# SE880_module_EFM32LG-STK3600.net
KiCad netlist of a schematic drawn in EAGLE
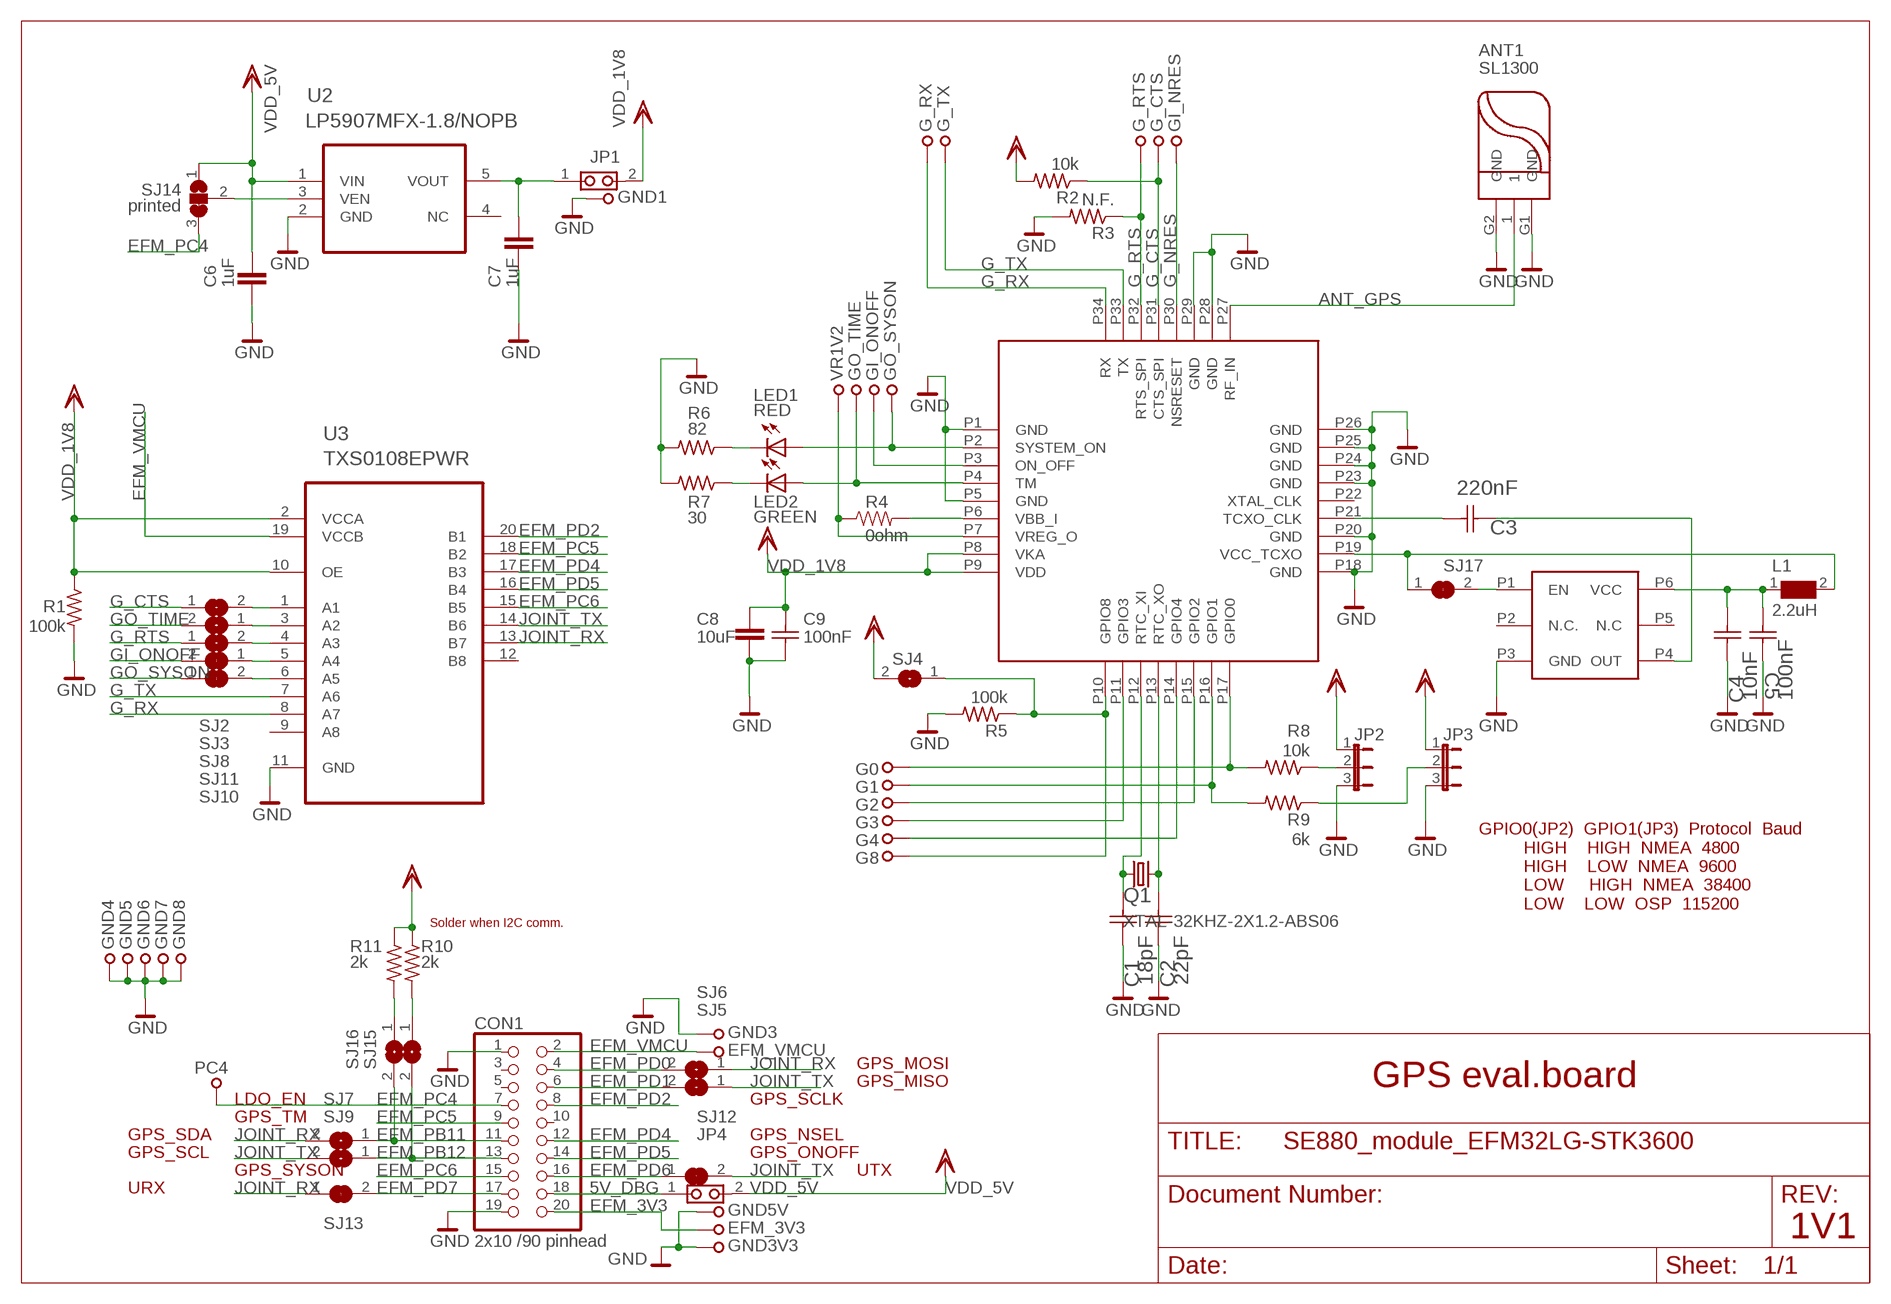
[diagram p0: schematic, sheet 1]

(export (version "E")
  (design (tool "Eeschema 10.0.6"))
  (components
    (comp (ref "ANT1")
      (value "SL1300")
      (footprint "eagle-import:SL1300")
      (libsource (lib "eagle-import") (part "SL1300"))
    )
    (comp (ref "C1")
      (value "18pF")
      (footprint "eagle-import:CAPC1005X60N")
      (libsource (lib "eagle-import") (part "CAP_GRM15"))
    )
    (comp (ref "C2")
      (value "22pF")
      (footprint "eagle-import:CAPC1005X60N")
      (libsource (lib "eagle-import") (part "CAP_GRM15"))
    )
    (comp (ref "C3")
      (value "220nF")
      (footprint "eagle-import:CAPC1005X60N")
      (libsource (lib "eagle-import") (part "CAP_GRM15"))
    )
    (comp (ref "C4")
      (value "10nF")
      (footprint "eagle-import:CAPC1005X60N")
      (libsource (lib "eagle-import") (part "CAP_GRM15"))
    )
    (comp (ref "C5")
      (value "100nF")
      (footprint "eagle-import:CAPC1005X60N")
      (libsource (lib "eagle-import") (part "CAP_GRM15"))
    )
    (comp (ref "C6")
      (value "1uF")
      (footprint "eagle-import:0603")
      (libsource (lib "eagle-import") (part "CAP-SMD0603"))
    )
    (comp (ref "C7")
      (value "1uF")
      (footprint "eagle-import:0603")
      (libsource (lib "eagle-import") (part "CAP-SMD0603"))
    )
    (comp (ref "C8")
      (value "10uF")
      (footprint "eagle-import:0603")
      (libsource (lib "eagle-import") (part "CAP-SMD0603"))
    )
    (comp (ref "C9")
      (value "100nF")
      (footprint "eagle-import:CAPC1005X60N")
      (libsource (lib "eagle-import") (part "CAP_GRM15"))
    )
    (comp (ref "CON1")
      (value "2x10 /90 pinhead")
      (footprint "eagle-import:2X10_90_FEMALE_EFM_MUTANT")
      (libsource (lib "eagle-import") (part "PINHD-2X10/90_FEMALE_EFM"))
    )
    (comp (ref "EFM_3V3")
      (value "TESTPOINT39MIL")
      (footprint "eagle-import:TESTPOINT1,0")
      (libsource (lib "eagle-import") (part "TESTPOINT39MIL"))
    )
    (comp (ref "EFM_VMCU")
      (value "TESTPOINT39MIL")
      (footprint "eagle-import:TESTPOINT1,0")
      (libsource (lib "eagle-import") (part "TESTPOINT39MIL"))
    )
    (comp (ref "G0")
      (value "TESTPOINT39MIL")
      (footprint "eagle-import:TESTPOINT1,0")
      (libsource (lib "eagle-import") (part "TESTPOINT39MIL"))
    )
    (comp (ref "G1")
      (value "TESTPOINT39MIL")
      (footprint "eagle-import:TESTPOINT1,0")
      (libsource (lib "eagle-import") (part "TESTPOINT39MIL"))
    )
    (comp (ref "G2")
      (value "TESTPOINT39MIL")
      (footprint "eagle-import:TESTPOINT1,0")
      (libsource (lib "eagle-import") (part "TESTPOINT39MIL"))
    )
    (comp (ref "G3")
      (value "TESTPOINT39MIL")
      (footprint "eagle-import:TESTPOINT1,0")
      (libsource (lib "eagle-import") (part "TESTPOINT39MIL"))
    )
    (comp (ref "G4")
      (value "TESTPOINT39MIL")
      (footprint "eagle-import:TESTPOINT1,0")
      (libsource (lib "eagle-import") (part "TESTPOINT39MIL"))
    )
    (comp (ref "G8")
      (value "TESTPOINT39MIL")
      (footprint "eagle-import:TESTPOINT1,0")
      (libsource (lib "eagle-import") (part "TESTPOINT39MIL"))
    )
    (comp (ref "GI_NRES")
      (value "TESTPOINT39MIL")
      (footprint "eagle-import:TESTPOINT1,0")
      (libsource (lib "eagle-import") (part "TESTPOINT39MIL"))
    )
    (comp (ref "GI_ONOFF")
      (value "TESTPOINT39MIL")
      (footprint "eagle-import:TESTPOINT1,0")
      (libsource (lib "eagle-import") (part "TESTPOINT39MIL"))
    )
    (comp (ref "GND1")
      (value "TESTPOINT39MIL")
      (footprint "eagle-import:TESTPOINT1,0")
      (libsource (lib "eagle-import") (part "TESTPOINT39MIL"))
    )
    (comp (ref "GND3")
      (value "TESTPOINT39MIL")
      (footprint "eagle-import:TESTPOINT1,0")
      (libsource (lib "eagle-import") (part "TESTPOINT39MIL"))
    )
    (comp (ref "GND3V3")
      (value "TESTPOINT39MIL")
      (footprint "eagle-import:TESTPOINT1,0")
      (libsource (lib "eagle-import") (part "TESTPOINT39MIL"))
    )
    (comp (ref "GND4")
      (value "TESTPOINT39MIL")
      (footprint "eagle-import:TESTPOINT1,0")
      (libsource (lib "eagle-import") (part "TESTPOINT39MIL"))
    )
    (comp (ref "GND5")
      (value "TESTPOINT39MIL")
      (footprint "eagle-import:TESTPOINT1,0")
      (libsource (lib "eagle-import") (part "TESTPOINT39MIL"))
    )
    (comp (ref "GND5V")
      (value "TESTPOINT39MIL")
      (footprint "eagle-import:TESTPOINT1,0")
      (libsource (lib "eagle-import") (part "TESTPOINT39MIL"))
    )
    (comp (ref "GND6")
      (value "TESTPOINT39MIL")
      (footprint "eagle-import:TESTPOINT1,0")
      (libsource (lib "eagle-import") (part "TESTPOINT39MIL"))
    )
    (comp (ref "GND7")
      (value "TESTPOINT39MIL")
      (footprint "eagle-import:TESTPOINT1,0")
      (libsource (lib "eagle-import") (part "TESTPOINT39MIL"))
    )
    (comp (ref "GND8")
      (value "TESTPOINT39MIL")
      (footprint "eagle-import:TESTPOINT1,0")
      (libsource (lib "eagle-import") (part "TESTPOINT39MIL"))
    )
    (comp (ref "GO_SYSON")
      (value "TESTPOINT39MIL")
      (footprint "eagle-import:TESTPOINT1,0")
      (libsource (lib "eagle-import") (part "TESTPOINT39MIL"))
    )
    (comp (ref "GO_TIME")
      (value "TESTPOINT39MIL")
      (footprint "eagle-import:TESTPOINT1,0")
      (libsource (lib "eagle-import") (part "TESTPOINT39MIL"))
    )
    (comp (ref "G_CTS")
      (value "TESTPOINT39MIL")
      (footprint "eagle-import:TESTPOINT1,0")
      (libsource (lib "eagle-import") (part "TESTPOINT39MIL"))
    )
    (comp (ref "G_RTS")
      (value "TESTPOINT39MIL")
      (footprint "eagle-import:TESTPOINT1,0")
      (libsource (lib "eagle-import") (part "TESTPOINT39MIL"))
    )
    (comp (ref "G_RX")
      (value "TESTPOINT39MIL")
      (footprint "eagle-import:TESTPOINT1,0")
      (libsource (lib "eagle-import") (part "TESTPOINT39MIL"))
    )
    (comp (ref "G_TX")
      (value "TESTPOINT39MIL")
      (footprint "eagle-import:TESTPOINT1,0")
      (libsource (lib "eagle-import") (part "TESTPOINT39MIL"))
    )
    (comp (ref "JP1")
      (value "JUMPER2-A")
      (footprint "eagle-import:PIN2-1R")
      (libsource (lib "eagle-import") (part "JUMPER2-A"))
    )
    (comp (ref "JP2")
      (value "jumper 2mm")
      (footprint "eagle-import:JP2")
      (libsource (lib "eagle-import") (part "JP2E"))
    )
    (comp (ref "JP3")
      (value "jumper 2mm")
      (footprint "eagle-import:JP2")
      (libsource (lib "eagle-import") (part "JP2E"))
    )
    (comp (ref "JP4")
      (value "JUMPER2-A")
      (footprint "eagle-import:PIN2-1R")
      (libsource (lib "eagle-import") (part "JUMPER2-A"))
    )
    (comp (ref "L1")
      (value "2.2uH")
      (footprint "eagle-import:WE-KI_1008_B")
      (libsource (lib "eagle-import") (part "WE-KI_1008_B"))
    )
    (comp (ref "LED1")
      (value "RED")
      (footprint "eagle-import:LED-0603")
      (libsource (lib "eagle-import") (part "LED0603"))
    )
    (comp (ref "LED2")
      (value "GREEN")
      (footprint "eagle-import:LED-0603")
      (libsource (lib "eagle-import") (part "LED0603"))
    )
    (comp (ref "PC4")
      (value "TESTPOINT39MIL")
      (footprint "eagle-import:TESTPOINT1,0")
      (libsource (lib "eagle-import") (part "TESTPOINT39MIL"))
    )
    (comp (ref "Q1")
      (value "XTAL-32KHZ-2X1.2-ABS06")
      (footprint "eagle-import:CRYSTAL-SMD-2X1.2-ABS06")
      (libsource (lib "eagle-import") (part "XTAL-32KHZ-2X1.2-ABS06"))
    )
    (comp (ref "Q3")
      (value "KT2520F16369ACW18TAN")
      (footprint "eagle-import:TCXO_2.5X2MM")
      (libsource (lib "eagle-import") (part "TCXO-KT2520-16M369"))
    )
    (comp (ref "R1")
      (value "100k")
      (footprint "eagle-import:R0402")
      (libsource (lib "eagle-import") (part "R-US_R0402"))
    )
    (comp (ref "R2")
      (value "10k")
      (footprint "eagle-import:R0402")
      (libsource (lib "eagle-import") (part "R-US_R0402"))
    )
    (comp (ref "R3")
      (value "N.F.")
      (footprint "eagle-import:R0402")
      (libsource (lib "eagle-import") (part "R-US_R0402"))
    )
    (comp (ref "R4")
      (value "0ohm")
      (footprint "eagle-import:0603-RES")
      (libsource (lib "eagle-import") (part "RESISTOR0603-RES"))
    )
    (comp (ref "R5")
      (value "100k")
      (footprint "eagle-import:R0402")
      (libsource (lib "eagle-import") (part "R-US_R0402"))
    )
    (comp (ref "R6")
      (value "82")
      (footprint "eagle-import:R0402")
      (libsource (lib "eagle-import") (part "R-US_R0402"))
    )
    (comp (ref "R7")
      (value "30")
      (footprint "eagle-import:R0402")
      (libsource (lib "eagle-import") (part "R-US_R0402"))
    )
    (comp (ref "R8")
      (value "10k")
      (footprint "eagle-import:R0402")
      (libsource (lib "eagle-import") (part "R-US_R0402"))
    )
    (comp (ref "R9")
      (value "6k")
      (footprint "eagle-import:R0402")
      (libsource (lib "eagle-import") (part "R-US_R0402"))
    )
    (comp (ref "R10")
      (value "2k")
      (footprint "eagle-import:R0402")
      (libsource (lib "eagle-import") (part "R-US_R0402"))
    )
    (comp (ref "R11")
      (value "2k")
      (footprint "eagle-import:R0402")
      (libsource (lib "eagle-import") (part "R-US_R0402"))
    )
    (comp (ref "SJ2")
      (value "printed")
      (footprint "eagle-import:JUMPER_SMD_SJ")
      (libsource (lib "eagle-import") (part "JUMPER_SMD"))
    )
    (comp (ref "SJ3")
      (value "printed")
      (footprint "eagle-import:JUMPER_SMD_SJ")
      (libsource (lib "eagle-import") (part "JUMPER_SMD"))
    )
    (comp (ref "SJ4")
      (value "printed")
      (footprint "eagle-import:JUMPER_SMD_SJ")
      (libsource (lib "eagle-import") (part "JUMPER_SMD"))
    )
    (comp (ref "SJ5")
      (value "printed")
      (footprint "eagle-import:JUMPER_SMD_SJ")
      (libsource (lib "eagle-import") (part "JUMPER_SMD"))
    )
    (comp (ref "SJ6")
      (value "printed")
      (footprint "eagle-import:JUMPER_SMD_SJ")
      (libsource (lib "eagle-import") (part "JUMPER_SMD"))
    )
    (comp (ref "SJ7")
      (value "printed")
      (footprint "eagle-import:JUMPER_SMD_SJ")
      (libsource (lib "eagle-import") (part "JUMPER_SMD"))
    )
    (comp (ref "SJ8")
      (value "printed")
      (footprint "eagle-import:JUMPER_SMD_SJ")
      (libsource (lib "eagle-import") (part "JUMPER_SMD"))
    )
    (comp (ref "SJ9")
      (value "printed")
      (footprint "eagle-import:JUMPER_SMD_SJ")
      (libsource (lib "eagle-import") (part "JUMPER_SMD"))
    )
    (comp (ref "SJ10")
      (value "printed")
      (footprint "eagle-import:JUMPER_SMD_SJ_1")
      (libsource (lib "eagle-import") (part "JUMPER_SMD_1"))
    )
    (comp (ref "SJ11")
      (value "printed")
      (footprint "eagle-import:JUMPER_SMD_SJ_1")
      (libsource (lib "eagle-import") (part "JUMPER_SMD_1"))
    )
    (comp (ref "SJ12")
      (value "printed")
      (footprint "eagle-import:JUMPER_SMD_SJ_1")
      (libsource (lib "eagle-import") (part "JUMPER_SMD_1"))
    )
    (comp (ref "SJ13")
      (value "printed")
      (footprint "eagle-import:JUMPER_SMD_SJ_1")
      (libsource (lib "eagle-import") (part "JUMPER_SMD_1"))
    )
    (comp (ref "SJ14")
      (value "printed")
      (footprint "eagle-import:JUMPER_SMD_SJ2A")
      (libsource (lib "eagle-import") (part "JUMPER_SMD_3A"))
    )
    (comp (ref "SJ15")
      (value "printed")
      (footprint "eagle-import:JUMPER_SMD_SJ")
      (libsource (lib "eagle-import") (part "JUMPER_SMD"))
    )
    (comp (ref "SJ16")
      (value "printed")
      (footprint "eagle-import:JUMPER_SMD_SJ")
      (libsource (lib "eagle-import") (part "JUMPER_SMD"))
    )
    (comp (ref "SJ17")
      (value "printed")
      (footprint "eagle-import:JUMPER_SMD_SJ_1")
      (libsource (lib "eagle-import") (part "JUMPER_SMD_1"))
    )
    (comp (ref "U1")
      (value "Telit SE880 GPS receiver")
      (footprint "eagle-import:LGA-34")
      (libsource (lib "eagle-import") (part "SE880"))
    )
    (comp (ref "U2")
      (value "LP5907MFX-1.8/NOPB")
      (footprint "eagle-import:SOT-23_5-NEW")
      (libsource (lib "eagle-import") (part "LP5907MFX-1.8/NOPB"))
    )
    (comp (ref "U3")
      (value "TXS0108EPWR")
      (footprint "eagle-import:SOP65P640X120-20N")
      (libsource (lib "eagle-import") (part "TXB0108PWR"))
    )
    (comp (ref "VR1V2")
      (value "TESTPOINT39MIL")
      (footprint "eagle-import:TESTPOINT1,0")
      (libsource (lib "eagle-import") (part "TESTPOINT39MIL"))
    )
  )
  (nets
    (net (code "1") (name "/5V_DBG") (class "Default")
      (node (ref "CON1") (pin "18") (pinfunction "18_18") (pintype "passive"))
      (node (ref "JP4") (pin "1") (pinfunction "A_1") (pintype "passive"))
    )
    (net (code "2") (name "/ANT_GPS") (class "Default")
      (node (ref "ANT1") (pin "1") (pinfunction "1_1") (pintype "bidirectional"))
      (node (ref "U1") (pin "P27") (pinfunction "RF_IN_P27") (pintype "bidirectional"))
    )
    (net (code "3") (name "/EFM_3V3") (class "Default")
      (node (ref "CON1") (pin "20") (pinfunction "20_20") (pintype "passive"))
      (node (ref "EFM_3V3") (pin "1") (pinfunction "P$1_1") (pintype "passive"))
    )
    (net (code "4") (name "/EFM_PB11") (class "Default")
      (node (ref "CON1") (pin "11") (pinfunction "11_11") (pintype "passive"))
      (node (ref "SJ16") (pin "2") (pinfunction "2_2") (pintype "passive"))
      (node (ref "SJ7") (pin "1") (pinfunction "1_1") (pintype "passive"))
    )
    (net (code "5") (name "/EFM_PB12") (class "Default")
      (node (ref "CON1") (pin "13") (pinfunction "13_13") (pintype "passive"))
      (node (ref "SJ15") (pin "2") (pinfunction "2_2") (pintype "passive"))
      (node (ref "SJ9") (pin "1") (pinfunction "1_1") (pintype "passive"))
    )
    (net (code "6") (name "/EFM_PC4") (class "Default")
      (node (ref "CON1") (pin "7") (pinfunction "7_7") (pintype "passive"))
      (node (ref "PC4") (pin "1") (pinfunction "P$1_1") (pintype "passive"))
      (node (ref "SJ14") (pin "3") (pinfunction "3_3") (pintype "passive"))
    )
    (net (code "7") (name "/EFM_PC5") (class "Default")
      (node (ref "CON1") (pin "9") (pinfunction "9_9") (pintype "passive"))
      (node (ref "U3") (pin "18") (pinfunction "B2_18") (pintype "bidirectional"))
    )
    (net (code "8") (name "/EFM_PC6") (class "Default")
      (node (ref "CON1") (pin "15") (pinfunction "15_15") (pintype "passive"))
      (node (ref "U3") (pin "15") (pinfunction "B5_15") (pintype "bidirectional"))
    )
    (net (code "9") (name "/EFM_PD0") (class "Default")
      (node (ref "CON1") (pin "4") (pinfunction "4_4") (pintype "passive"))
      (node (ref "SJ6") (pin "2") (pinfunction "2_2") (pintype "passive"))
    )
    (net (code "10") (name "/EFM_PD1") (class "Default")
      (node (ref "CON1") (pin "6") (pinfunction "6_6") (pintype "passive"))
      (node (ref "SJ5") (pin "2") (pinfunction "2_2") (pintype "passive"))
    )
    (net (code "11") (name "/EFM_PD2") (class "Default")
      (node (ref "CON1") (pin "8") (pinfunction "8_8") (pintype "passive"))
      (node (ref "U3") (pin "20") (pinfunction "B1_20") (pintype "bidirectional"))
    )
    (net (code "12") (name "/EFM_PD4") (class "Default")
      (node (ref "CON1") (pin "12") (pinfunction "12_12") (pintype "passive"))
      (node (ref "U3") (pin "17") (pinfunction "B3_17") (pintype "bidirectional"))
    )
    (net (code "13") (name "/EFM_PD5") (class "Default")
      (node (ref "CON1") (pin "14") (pinfunction "14_14") (pintype "passive"))
      (node (ref "U3") (pin "16") (pinfunction "B4_16") (pintype "bidirectional"))
    )
    (net (code "14") (name "/EFM_PD6") (class "Default")
      (node (ref "CON1") (pin "16") (pinfunction "16_16") (pintype "passive"))
      (node (ref "SJ12") (pin "1") (pinfunction "1_1") (pintype "passive"))
    )
    (net (code "15") (name "/EFM_PD7") (class "Default")
      (node (ref "CON1") (pin "17") (pinfunction "17_17") (pintype "passive"))
      (node (ref "SJ13") (pin "2") (pinfunction "2_2") (pintype "passive"))
    )
    (net (code "16") (name "/EFM_VMCU") (class "Default")
      (node (ref "CON1") (pin "2") (pinfunction "2_2") (pintype "passive"))
      (node (ref "EFM_VMCU") (pin "1") (pinfunction "P$1_1") (pintype "passive"))
      (node (ref "U3") (pin "19") (pinfunction "VCCB_19") (pintype "power_in"))
    )
    (net (code "17") (name "/GI_ONOFF") (class "Default")
      (node (ref "GI_ONOFF") (pin "1") (pinfunction "P$1_1") (pintype "passive"))
      (node (ref "SJ11") (pin "2") (pinfunction "2_2") (pintype "passive"))
      (node (ref "U1") (pin "P3") (pinfunction "ON_OFF_P3") (pintype "bidirectional"))
    )
    (net (code "18") (name "/GO_SYSON") (class "Default")
      (node (ref "GO_SYSON") (pin "1") (pinfunction "P$1_1") (pintype "passive"))
      (node (ref "LED1") (pin "A") (pinfunction "A_A") (pintype "passive"))
      (node (ref "SJ10") (pin "1") (pinfunction "1_1") (pintype "passive"))
      (node (ref "U1") (pin "P2") (pinfunction "SYSTEM_ON_P2") (pintype "bidirectional"))
    )
    (net (code "19") (name "/GO_TIME") (class "Default")
      (node (ref "GO_TIME") (pin "1") (pinfunction "P$1_1") (pintype "passive"))
      (node (ref "LED2") (pin "A") (pinfunction "A_A") (pintype "passive"))
      (node (ref "SJ3") (pin "2") (pinfunction "2_2") (pintype "passive"))
      (node (ref "U1") (pin "P4") (pinfunction "TM_P4") (pintype "bidirectional"))
    )
    (net (code "20") (name "/G_CTS") (class "Default")
      (node (ref "G_CTS") (pin "1") (pinfunction "P$1_1") (pintype "passive"))
      (node (ref "R2") (pin "1") (pinfunction "1_1") (pintype "passive"))
      (node (ref "SJ2") (pin "1") (pinfunction "1_1") (pintype "passive"))
      (node (ref "U1") (pin "P31") (pinfunction "CTS_SPI_P31") (pintype "bidirectional"))
    )
    (net (code "21") (name "/G_NRES") (class "Default")
      (node (ref "GI_NRES") (pin "1") (pinfunction "P$1_1") (pintype "passive"))
      (node (ref "U1") (pin "P30") (pinfunction "NSRESET_P30") (pintype "bidirectional"))
    )
    (net (code "22") (name "/G_RTS") (class "Default")
      (node (ref "G_RTS") (pin "1") (pinfunction "P$1_1") (pintype "passive"))
      (node (ref "R3") (pin "1") (pinfunction "1_1") (pintype "passive"))
      (node (ref "SJ8") (pin "1") (pinfunction "1_1") (pintype "passive"))
      (node (ref "U1") (pin "P32") (pinfunction "RTS_SPI_P32") (pintype "bidirectional"))
    )
    (net (code "23") (name "/G_RX") (class "Default")
      (node (ref "G_RX") (pin "1") (pinfunction "P$1_1") (pintype "passive"))
      (node (ref "U1") (pin "P34") (pinfunction "RX_P34") (pintype "bidirectional"))
      (node (ref "U3") (pin "8") (pinfunction "A7_8") (pintype "bidirectional"))
    )
    (net (code "24") (name "/G_TX") (class "Default")
      (node (ref "G_TX") (pin "1") (pinfunction "P$1_1") (pintype "passive"))
      (node (ref "U1") (pin "P33") (pinfunction "TX_P33") (pintype "bidirectional"))
      (node (ref "U3") (pin "7") (pinfunction "A6_7") (pintype "bidirectional"))
    )
    (net (code "25") (name "/JOINT_RX") (class "Default")
      (node (ref "SJ13") (pin "1") (pinfunction "1_1") (pintype "passive"))
      (node (ref "SJ6") (pin "1") (pinfunction "1_1") (pintype "passive"))
      (node (ref "SJ7") (pin "2") (pinfunction "2_2") (pintype "passive"))
      (node (ref "U3") (pin "13") (pinfunction "B7_13") (pintype "bidirectional"))
    )
    (net (code "26") (name "/JOINT_TX") (class "Default")
      (node (ref "SJ12") (pin "2") (pinfunction "2_2") (pintype "passive"))
      (node (ref "SJ5") (pin "1") (pinfunction "1_1") (pintype "passive"))
      (node (ref "SJ9") (pin "2") (pinfunction "2_2") (pintype "passive"))
      (node (ref "U3") (pin "14") (pinfunction "B6_14") (pintype "bidirectional"))
    )
    (net (code "27") (name "GND") (class "Default")
      (node (ref "ANT1") (pin "G1") (pinfunction "GND_G1") (pintype "power_in"))
      (node (ref "ANT1") (pin "G2") (pinfunction "GND_G2") (pintype "power_in"))
      (node (ref "C1") (pin "2") (pinfunction "C2_2") (pintype "passive"))
      (node (ref "C2") (pin "2") (pinfunction "C2_2") (pintype "passive"))
      (node (ref "C4") (pin "2") (pinfunction "C2_2") (pintype "passive"))
      (node (ref "C5") (pin "2") (pinfunction "C2_2") (pintype "passive"))
      (node (ref "C6") (pin "1") (pinfunction "1_1") (pintype "passive"))
      (node (ref "C7") (pin "1") (pinfunction "1_1") (pintype "passive"))
      (node (ref "C8") (pin "1") (pinfunction "1_1") (pintype "passive"))
      (node (ref "C9") (pin "2") (pinfunction "C2_2") (pintype "passive"))
      (node (ref "CON1") (pin "1") (pinfunction "1_1") (pintype "passive"))
      (node (ref "CON1") (pin "19") (pinfunction "19_19") (pintype "passive"))
      (node (ref "GND1") (pin "1") (pinfunction "P$1_1") (pintype "passive"))
      (node (ref "GND3") (pin "1") (pinfunction "P$1_1") (pintype "passive"))
      (node (ref "GND3V3") (pin "1") (pinfunction "P$1_1") (pintype "passive"))
      (node (ref "GND4") (pin "1") (pinfunction "P$1_1") (pintype "passive"))
      (node (ref "GND5") (pin "1") (pinfunction "P$1_1") (pintype "passive"))
      (node (ref "GND5V") (pin "1") (pinfunction "P$1_1") (pintype "passive"))
      (node (ref "GND6") (pin "1") (pinfunction "P$1_1") (pintype "passive"))
      (node (ref "GND7") (pin "1") (pinfunction "P$1_1") (pintype "passive"))
      (node (ref "GND8") (pin "1") (pinfunction "P$1_1") (pintype "passive"))
      (node (ref "JP2") (pin "3") (pinfunction "3_3") (pintype "passive"))
      (node (ref "JP3") (pin "3") (pinfunction "3_3") (pintype "passive"))
      (node (ref "Q3") (pin "P3") (pinfunction "GND_P3") (pintype "power_in"))
      (node (ref "R1") (pin "2") (pinfunction "2_2") (pintype "passive"))
      (node (ref "R3") (pin "2") (pinfunction "2_2") (pintype "passive"))
      (node (ref "R5") (pin "2") (pinfunction "2_2") (pintype "passive"))
      (node (ref "R6") (pin "2") (pinfunction "2_2") (pintype "passive"))
      (node (ref "R7") (pin "2") (pinfunction "2_2") (pintype "passive"))
      (node (ref "U1") (pin "P1") (pinfunction "GND_P1") (pintype "bidirectional"))
      (node (ref "U1") (pin "P18") (pinfunction "GND_P18") (pintype "bidirectional"))
      (node (ref "U1") (pin "P20") (pinfunction "GND_P20") (pintype "bidirectional"))
      (node (ref "U1") (pin "P23") (pinfunction "GND_P23") (pintype "bidirectional"))
      (node (ref "U1") (pin "P24") (pinfunction "GND_P24") (pintype "bidirectional"))
      (node (ref "U1") (pin "P25") (pinfunction "GND_P25") (pintype "bidirectional"))
      (node (ref "U1") (pin "P26") (pinfunction "GND_P26") (pintype "bidirectional"))
      (node (ref "U1") (pin "P28") (pinfunction "GND_P28") (pintype "bidirectional"))
      (node (ref "U1") (pin "P29") (pinfunction "GND_P29") (pintype "bidirectional"))
      (node (ref "U1") (pin "P5") (pinfunction "GND_P5") (pintype "bidirectional"))
      (node (ref "U2") (pin "2") (pinfunction "GND_2") (pintype "passive"))
      (node (ref "U3") (pin "11") (pinfunction "GND_11") (pintype "passive"))
    )
    (net (code "28") (name "Net-(C1-C1)") (class "Default")
      (node (ref "C1") (pin "1") (pinfunction "C1_1") (pintype "passive"))
      (node (ref "Q1") (pin "P$1") (pinfunction "1_P$1") (pintype "passive"))
      (node (ref "U1") (pin "P12") (pinfunction "RTC_XI_P12") (pintype "bidirectional"))
    )
    (net (code "29") (name "Net-(C2-C1)") (class "Default")
      (node (ref "C2") (pin "1") (pinfunction "C1_1") (pintype "passive"))
      (node (ref "Q1") (pin "P$2") (pinfunction "2_P$2") (pintype "passive"))
      (node (ref "U1") (pin "P13") (pinfunction "RTC_XO_P13") (pintype "bidirectional"))
    )
    (net (code "30") (name "Net-(C3-C1)") (class "Default")
      (node (ref "C3") (pin "1") (pinfunction "C1_1") (pintype "passive"))
      (node (ref "U1") (pin "P21") (pinfunction "TCXO_CLK_P21") (pintype "bidirectional"))
    )
    (net (code "31") (name "Net-(C3-C2)") (class "Default")
      (node (ref "C3") (pin "2") (pinfunction "C2_2") (pintype "passive"))
      (node (ref "Q3") (pin "P4") (pinfunction "OUT_P4") (pintype "output"))
    )
    (net (code "32") (name "Net-(C4-C1)") (class "Default")
      (node (ref "C4") (pin "1") (pinfunction "C1_1") (pintype "passive"))
      (node (ref "C5") (pin "1") (pinfunction "C1_1") (pintype "passive"))
      (node (ref "L1") (pin "1") (pinfunction "1_1") (pintype "passive"))
      (node (ref "Q3") (pin "P6") (pinfunction "VCC_P6") (pintype "power_in"))
    )
    (net (code "33") (name "Net-(G0-P$1)") (class "Default")
      (node (ref "G0") (pin "1") (pinfunction "P$1_1") (pintype "passive"))
      (node (ref "R8") (pin "2") (pinfunction "2_2") (pintype "passive"))
      (node (ref "U1") (pin "P17") (pinfunction "GPIO0_P17") (pintype "bidirectional"))
    )
    (net (code "34") (name "Net-(G1-P$1)") (class "Default")
      (node (ref "G1") (pin "1") (pinfunction "P$1_1") (pintype "passive"))
      (node (ref "R9") (pin "2") (pinfunction "2_2") (pintype "passive"))
      (node (ref "U1") (pin "P16") (pinfunction "GPIO1_P16") (pintype "bidirectional"))
    )
    (net (code "35") (name "Net-(G2-P$1)") (class "Default")
      (node (ref "G2") (pin "1") (pinfunction "P$1_1") (pintype "passive"))
      (node (ref "U1") (pin "P15") (pinfunction "GPIO2_P15") (pintype "bidirectional"))
    )
    (net (code "36") (name "Net-(G3-P$1)") (class "Default")
      (node (ref "G3") (pin "1") (pinfunction "P$1_1") (pintype "passive"))
      (node (ref "U1") (pin "P11") (pinfunction "GPIO3_P11") (pintype "bidirectional"))
    )
    (net (code "37") (name "Net-(G4-P$1)") (class "Default")
      (node (ref "G4") (pin "1") (pinfunction "P$1_1") (pintype "passive"))
      (node (ref "U1") (pin "P14") (pinfunction "GPIO4_P14") (pintype "bidirectional"))
    )
    (net (code "38") (name "Net-(G8-P$1)") (class "Default")
      (node (ref "G8") (pin "1") (pinfunction "P$1_1") (pintype "passive"))
      (node (ref "R5") (pin "1") (pinfunction "1_1") (pintype "passive"))
      (node (ref "SJ4") (pin "1") (pinfunction "1_1") (pintype "passive"))
      (node (ref "U1") (pin "P10") (pinfunction "GPIO8_P10") (pintype "bidirectional"))
    )
    (net (code "39") (name "Net-(JP1-A)") (class "Default")
      (node (ref "C7") (pin "2") (pinfunction "2_2") (pintype "passive"))
      (node (ref "JP1") (pin "1") (pinfunction "A_1") (pintype "passive"))
      (node (ref "U2") (pin "5") (pinfunction "VOUT_5") (pintype "output"))
    )
    (net (code "40") (name "Net-(JP2-Pad2)") (class "Default")
      (node (ref "JP2") (pin "2") (pinfunction "2_2") (pintype "passive"))
      (node (ref "R8") (pin "1") (pinfunction "1_1") (pintype "passive"))
    )
    (net (code "41") (name "Net-(JP3-Pad2)") (class "Default")
      (node (ref "JP3") (pin "2") (pinfunction "2_2") (pintype "passive"))
      (node (ref "R9") (pin "1") (pinfunction "1_1") (pintype "passive"))
    )
    (net (code "42") (name "Net-(LED1-PadC)") (class "Default")
      (node (ref "LED1") (pin "C") (pinfunction "C_C") (pintype "passive"))
      (node (ref "R6") (pin "1") (pinfunction "1_1") (pintype "passive"))
    )
    (net (code "43") (name "Net-(LED2-PadC)") (class "Default")
      (node (ref "LED2") (pin "C") (pinfunction "C_C") (pintype "passive"))
      (node (ref "R7") (pin "1") (pinfunction "1_1") (pintype "passive"))
    )
    (net (code "44") (name "Net-(Q3-EN)") (class "Default")
      (node (ref "Q3") (pin "P1") (pinfunction "EN_P1") (pintype "bidirectional"))
      (node (ref "SJ17") (pin "2") (pinfunction "2_2") (pintype "passive"))
    )
    (net (code "45") (name "Net-(R10-Pad2)") (class "Default")
      (node (ref "R10") (pin "2") (pinfunction "2_2") (pintype "passive"))
      (node (ref "SJ15") (pin "1") (pinfunction "1_1") (pintype "passive"))
    )
    (net (code "46") (name "Net-(R11-Pad2)") (class "Default")
      (node (ref "R11") (pin "2") (pinfunction "2_2") (pintype "passive"))
      (node (ref "SJ16") (pin "1") (pinfunction "1_1") (pintype "passive"))
    )
    (net (code "47") (name "Net-(U1-VBB_I)") (class "Default")
      (node (ref "R4") (pin "2") (pinfunction "2_2") (pintype "passive"))
      (node (ref "U1") (pin "P6") (pinfunction "VBB_I_P6") (pintype "bidirectional"))
    )
    (net (code "48") (name "Net-(U1-VCC_TCXO)") (class "Default")
      (node (ref "L1") (pin "2") (pinfunction "2_2") (pintype "passive"))
      (node (ref "SJ17") (pin "1") (pinfunction "1_1") (pintype "passive"))
      (node (ref "U1") (pin "P19") (pinfunction "VCC_TCXO_P19") (pintype "bidirectional"))
    )
    (net (code "49") (name "Net-(U1-VREG_O)") (class "Default")
      (node (ref "R4") (pin "1") (pinfunction "1_1") (pintype "passive"))
      (node (ref "U1") (pin "P7") (pinfunction "VREG_O_P7") (pintype "bidirectional"))
      (node (ref "VR1V2") (pin "1") (pinfunction "P$1_1") (pintype "passive"))
    )
    (net (code "50") (name "Net-(U2-VEN)") (class "Default")
      (node (ref "SJ14") (pin "2") (pinfunction "2_2") (pintype "passive"))
      (node (ref "U2") (pin "3") (pinfunction "VEN_3") (pintype "input"))
    )
    (net (code "51") (name "Net-(U3-A1)") (class "Default")
      (node (ref "SJ2") (pin "2") (pinfunction "2_2") (pintype "passive"))
      (node (ref "U3") (pin "1") (pinfunction "A1_1") (pintype "bidirectional"))
    )
    (net (code "52") (name "Net-(U3-A2)") (class "Default")
      (node (ref "SJ3") (pin "1") (pinfunction "1_1") (pintype "passive"))
      (node (ref "U3") (pin "3") (pinfunction "A2_3") (pintype "bidirectional"))
    )
    (net (code "53") (name "Net-(U3-A3)") (class "Default")
      (node (ref "SJ8") (pin "2") (pinfunction "2_2") (pintype "passive"))
      (node (ref "U3") (pin "4") (pinfunction "A3_4") (pintype "bidirectional"))
    )
    (net (code "54") (name "Net-(U3-A4)") (class "Default")
      (node (ref "SJ11") (pin "1") (pinfunction "1_1") (pintype "passive"))
      (node (ref "U3") (pin "5") (pinfunction "A4_5") (pintype "bidirectional"))
    )
    (net (code "55") (name "Net-(U3-A5)") (class "Default")
      (node (ref "SJ10") (pin "2") (pinfunction "2_2") (pintype "passive"))
      (node (ref "U3") (pin "6") (pinfunction "A5_6") (pintype "bidirectional"))
    )
    (net (code "56") (name "VDD_1V8") (class "Default")
      (node (ref "C8") (pin "2") (pinfunction "2_2") (pintype "passive"))
      (node (ref "C9") (pin "1") (pinfunction "C1_1") (pintype "passive"))
      (node (ref "JP1") (pin "2") (pinfunction "B_2") (pintype "passive"))
      (node (ref "JP2") (pin "1") (pinfunction "1_1") (pintype "passive"))
      (node (ref "JP3") (pin "1") (pinfunction "1_1") (pintype "passive"))
      (node (ref "R1") (pin "1") (pinfunction "1_1") (pintype "passive"))
      (node (ref "R10") (pin "1") (pinfunction "1_1") (pintype "passive"))
      (node (ref "R11") (pin "1") (pinfunction "1_1") (pintype "passive"))
      (node (ref "R2") (pin "2") (pinfunction "2_2") (pintype "passive"))
      (node (ref "SJ4") (pin "2") (pinfunction "2_2") (pintype "passive"))
      (node (ref "U1") (pin "P8") (pinfunction "VKA_P8") (pintype "bidirectional"))
      (node (ref "U1") (pin "P9") (pinfunction "VDD_P9") (pintype "bidirectional"))
      (node (ref "U3") (pin "10") (pinfunction "OE_10") (pintype "input"))
      (node (ref "U3") (pin "2") (pinfunction "VCCA_2") (pintype "power_in"))
    )
    (net (code "57") (name "VDD_5V") (class "Default")
      (node (ref "C6") (pin "2") (pinfunction "2_2") (pintype "passive"))
      (node (ref "JP4") (pin "2") (pinfunction "B_2") (pintype "passive"))
      (node (ref "SJ14") (pin "1") (pinfunction "1_1") (pintype "passive"))
      (node (ref "U2") (pin "1") (pinfunction "VIN_1") (pintype "power_in"))
    )
    (net (code "58") (name "unconnected-(CON1-Pad3)") (class "Default")
      (node (ref "CON1") (pin "3") (pinfunction "3_3") (pintype "passive"))
    )
    (net (code "59") (name "unconnected-(CON1-Pad5)") (class "Default")
      (node (ref "CON1") (pin "5") (pinfunction "5_5") (pintype "passive"))
    )
    (net (code "60") (name "unconnected-(CON1-Pad10)") (class "Default")
      (node (ref "CON1") (pin "10") (pinfunction "10_10") (pintype "passive"))
    )
    (net (code "61") (name "unconnected-(Q3-N.C-PadP5)") (class "Default")
      (node (ref "Q3") (pin "P5") (pinfunction "N.C_P5") (pintype "no_connect"))
    )
    (net (code "62") (name "unconnected-(Q3-N.C.-PadP2)") (class "Default")
      (node (ref "Q3") (pin "P2") (pinfunction "N.C._P2") (pintype "no_connect"))
    )
    (net (code "63") (name "unconnected-(U1-XTAL_CLK-PadP22)") (class "Default")
      (node (ref "U1") (pin "P22") (pinfunction "XTAL_CLK_P22") (pintype "bidirectional"))
    )
    (net (code "64") (name "unconnected-(U2-NC-Pad4)") (class "Default")
      (node (ref "U2") (pin "4") (pinfunction "NC_4") (pintype "no_connect"))
    )
    (net (code "65") (name "unconnected-(U3-A8-Pad9)") (class "Default")
      (node (ref "U3") (pin "9") (pinfunction "A8_9") (pintype "bidirectional"))
    )
    (net (code "66") (name "unconnected-(U3-B8-Pad12)") (class "Default")
      (node (ref "U3") (pin "12") (pinfunction "B8_12") (pintype "bidirectional"))
    )
  )
)
